# guider-shield.net
KiCad netlist of a schematic drawn in EAGLE
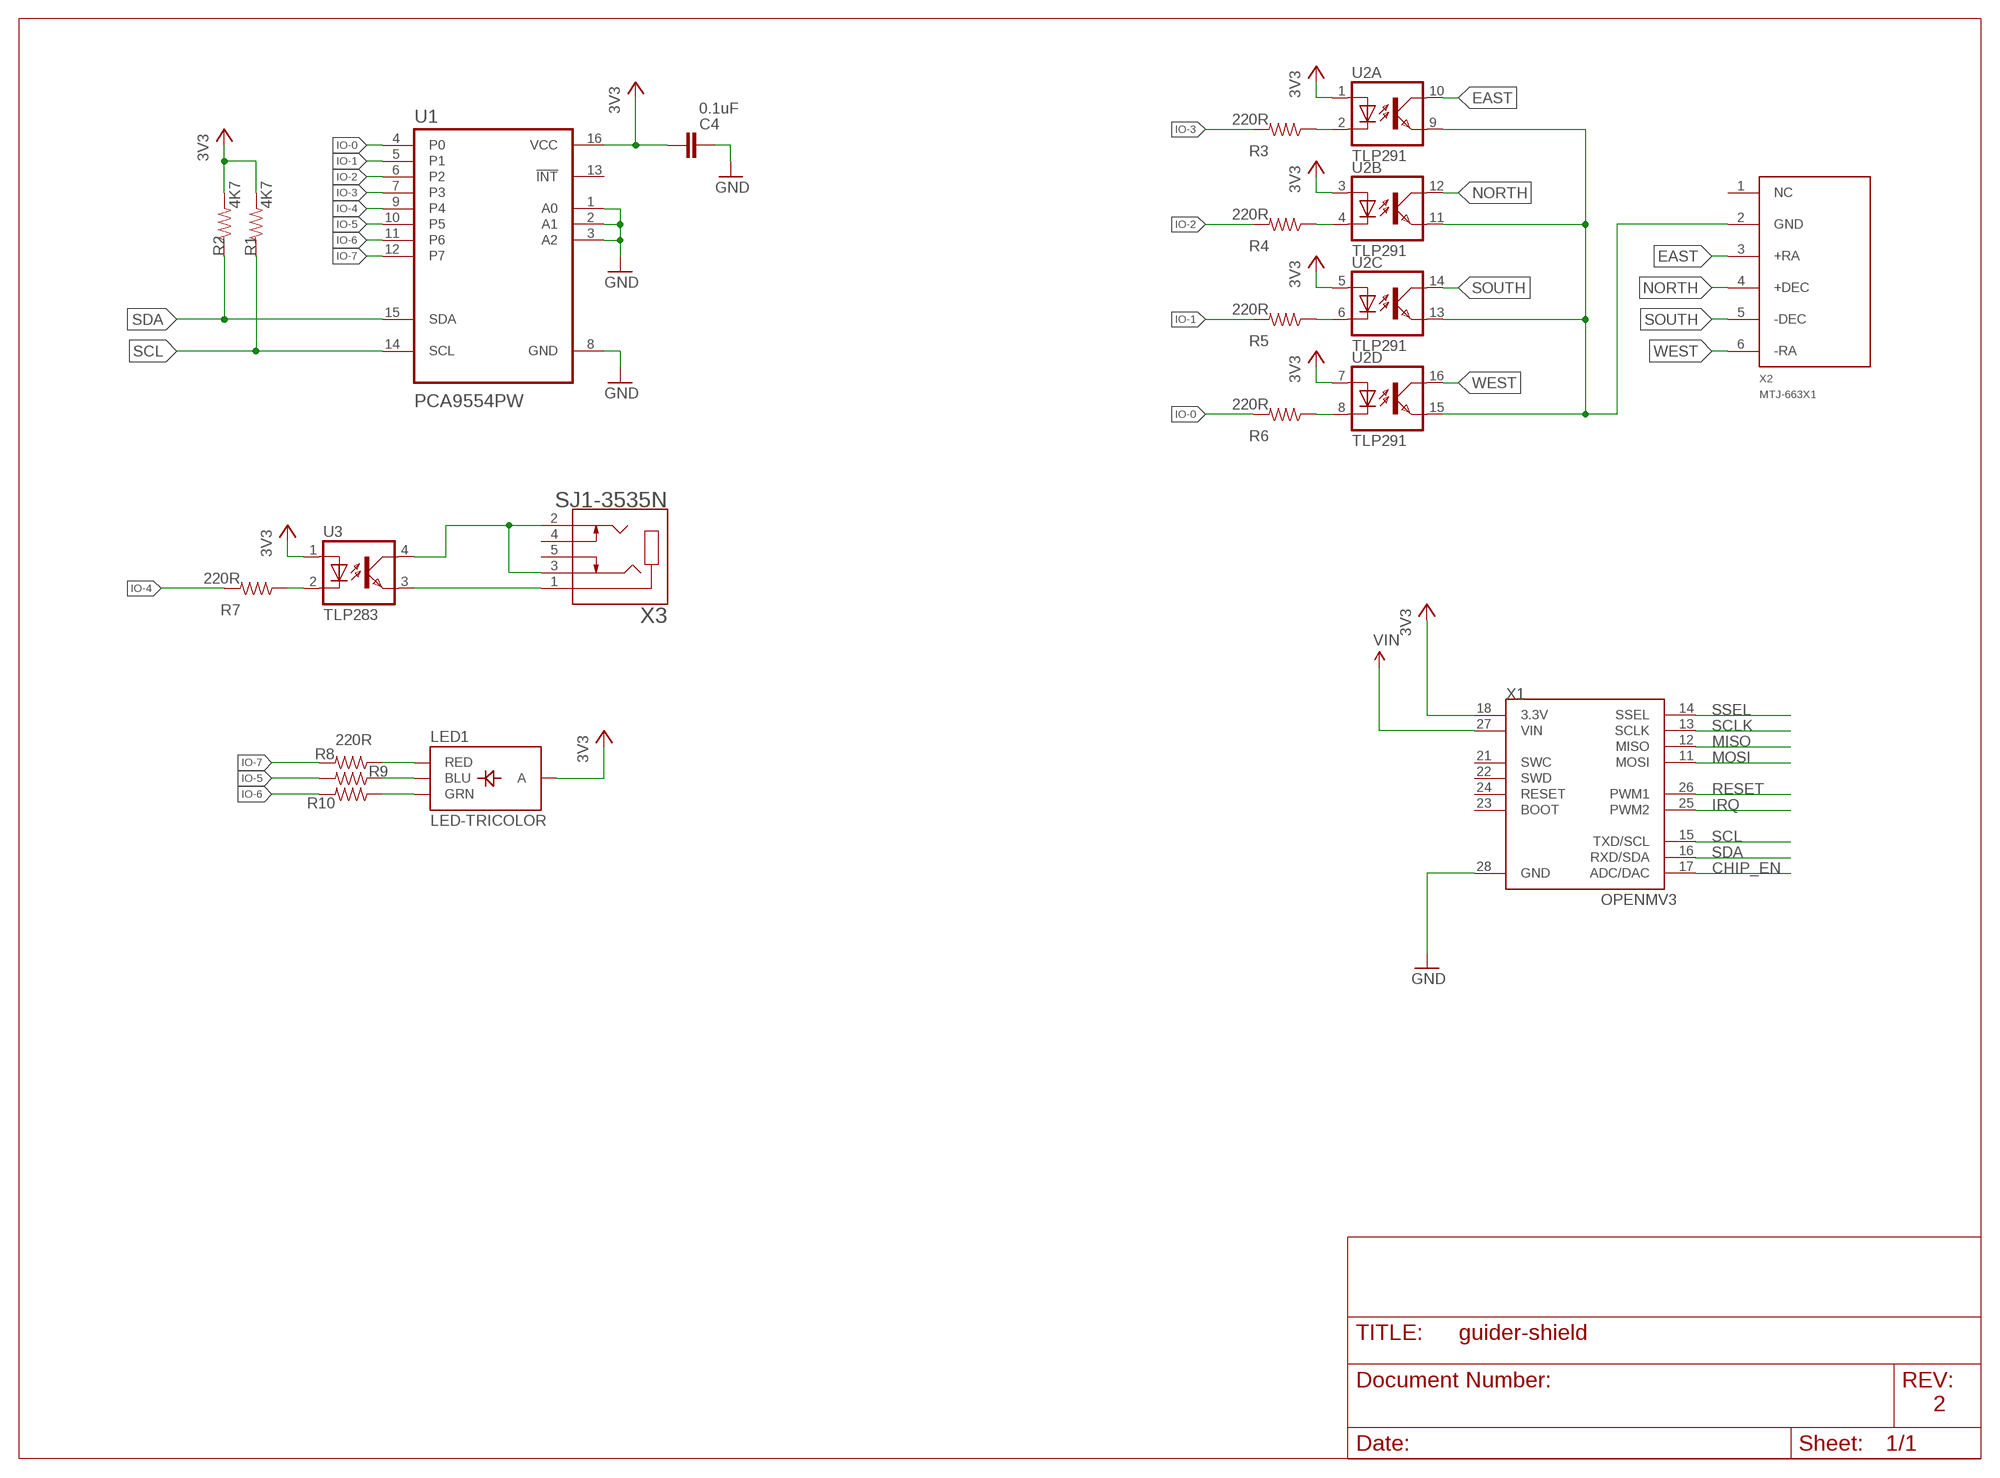
[diagram p0: schematic, sheet 1]

(export (version "E")
  (design (tool "Eeschema 10.0.6"))
  (components
    (comp (ref "C4")
      (value "0.1uF")
      (footprint "eagle-import:0603-CAP")
      (libsource (lib "eagle-import") (part "CAP0603-CAP"))
    )
    (comp (ref "LED1")
      (value "LED-TRICOLOR")
      (footprint "eagle-import:LED-TRICOLOR-SMD")
      (libsource (lib "eagle-import") (part "LED-TRICOLOR"))
    )
    (comp (ref "R1")
      (value "4K7")
      (footprint "eagle-import:0603-RES")
      (libsource (lib "eagle-import") (part "RESISTOR0603-RES"))
    )
    (comp (ref "R2")
      (value "4K7")
      (footprint "eagle-import:0603-RES")
      (libsource (lib "eagle-import") (part "RESISTOR0603-RES"))
    )
    (comp (ref "R3")
      (value "220R")
      (footprint "eagle-import:0603-RES")
      (libsource (lib "eagle-import") (part "RESISTOR0603-RES"))
    )
    (comp (ref "R4")
      (value "220R")
      (footprint "eagle-import:0603-RES")
      (libsource (lib "eagle-import") (part "RESISTOR0603-RES"))
    )
    (comp (ref "R5")
      (value "220R")
      (footprint "eagle-import:0603-RES")
      (libsource (lib "eagle-import") (part "RESISTOR0603-RES"))
    )
    (comp (ref "R6")
      (value "220R")
      (footprint "eagle-import:0603-RES")
      (libsource (lib "eagle-import") (part "RESISTOR0603-RES"))
    )
    (comp (ref "R7")
      (value "220R")
      (footprint "eagle-import:0603-RES")
      (libsource (lib "eagle-import") (part "RESISTOR0603-RES"))
    )
    (comp (ref "R8")
      (value "220R")
      (footprint "eagle-import:0603-RES")
      (libsource (lib "eagle-import") (part "RESISTOR0603-RES"))
    )
    (comp (ref "R9")
      (value "220R")
      (footprint "eagle-import:0603-RES")
      (libsource (lib "eagle-import") (part "RESISTOR0603-RES"))
    )
    (comp (ref "R10")
      (value "220R")
      (footprint "eagle-import:0603-RES")
      (libsource (lib "eagle-import") (part "RESISTOR0603-RES"))
    )
    (comp (ref "U1")
      (value "PCA9554PW")
      (footprint "eagle-import:SOP65P640X120-16N")
      (fields (field (name "MF") "Texas Instruments"))
      (libsource (lib "eagle-import") (part "PCA9554PW"))
    )
    (comp (ref "U2")
      (value "TLP291")
      (footprint "eagle-import:SO016")
      (libsource (lib "eagle-import") (part "TLP283-4-SO016"))
    )
    (comp (ref "U3")
      (value "TLP283")
      (footprint "eagle-import:MINI-FLAT-4")
      (libsource (lib "eagle-import") (part "TLP283"))
    )
    (comp (ref "X1")
      (value "OPENMV3")
      (footprint "eagle-import:OPENMV3")
      (libsource (lib "eagle-import") (part "OPENMV3"))
    )
    (comp (ref "X2")
      (value "MTJ-663X1")
      (footprint "eagle-import:MTJ-663X1")
      (libsource (lib "eagle-import") (part "ST-4-MTJ-663X1"))
    )
    (comp (ref "X3")
      (value "SJ1-3535N")
      (footprint "eagle-import:CUI_SJ1-3535N")
      (fields (field (name "MF") "CUI Devices"))
      (libsource (lib "eagle-import") (part "SJ1-3535N"))
    )
  )
  (nets
    (net (code "1") (name "/CHIP_EN") (class "Default")
      (node (ref "X1") (pin "17") (pinfunction "ADC/DAC_17") (pintype "bidirectional"))
    )
    (net (code "2") (name "/IRQ") (class "Default")
      (node (ref "X1") (pin "25") (pinfunction "PWM2_25") (pintype "bidirectional"))
    )
    (net (code "3") (name "/MISO") (class "Default")
      (node (ref "X1") (pin "12") (pinfunction "MISO_12") (pintype "bidirectional"))
    )
    (net (code "4") (name "/MOSI") (class "Default")
      (node (ref "X1") (pin "11") (pinfunction "MOSI_11") (pintype "bidirectional"))
    )
    (net (code "5") (name "/RESET") (class "Default")
      (node (ref "X1") (pin "26") (pinfunction "PWM1_26") (pintype "bidirectional"))
    )
    (net (code "6") (name "/SCLK") (class "Default")
      (node (ref "X1") (pin "13") (pinfunction "SCLK_13") (pintype "bidirectional"))
    )
    (net (code "7") (name "/SSEL") (class "Default")
      (node (ref "X1") (pin "14") (pinfunction "SSEL_14") (pintype "bidirectional"))
    )
    (net (code "8") (name "3V3") (class "Default")
      (node (ref "C4") (pin "1") (pinfunction "1_1") (pintype "passive"))
      (node (ref "LED1") (pin "A") (pinfunction "A_A") (pintype "bidirectional"))
      (node (ref "R1") (pin "2") (pinfunction "2_2") (pintype "passive"))
      (node (ref "R2") (pin "2") (pinfunction "2_2") (pintype "passive"))
      (node (ref "U1") (pin "16") (pinfunction "VCC_16") (pintype "power_in"))
      (node (ref "U2") (pin "1") (pinfunction "A_1") (pintype "passive"))
      (node (ref "U2") (pin "3") (pinfunction "A_3") (pintype "passive"))
      (node (ref "U2") (pin "5") (pinfunction "A_5") (pintype "passive"))
      (node (ref "U2") (pin "7") (pinfunction "A_7") (pintype "passive"))
      (node (ref "U3") (pin "1") (pinfunction "A_1") (pintype "passive"))
      (node (ref "X1") (pin "18") (pinfunction "3.3V_18") (pintype "power_in"))
    )
    (net (code "9") (name "EAST") (class "Default")
      (node (ref "U2") (pin "10") (pinfunction "COL_10") (pintype "passive"))
      (node (ref "X2") (pin "3") (pinfunction "+RA_3") (pintype "input"))
    )
    (net (code "10") (name "GND") (class "Default")
      (node (ref "C4") (pin "2") (pinfunction "2_2") (pintype "passive"))
      (node (ref "U1") (pin "1") (pinfunction "A0_1") (pintype "input"))
      (node (ref "U1") (pin "2") (pinfunction "A1_2") (pintype "input"))
      (node (ref "U1") (pin "3") (pinfunction "A2_3") (pintype "input"))
      (node (ref "U1") (pin "8") (pinfunction "GND_8") (pintype "power_in"))
      (node (ref "X1") (pin "28") (pinfunction "GND_28") (pintype "power_in"))
    )
    (net (code "11") (name "IO-0") (class "Default")
      (node (ref "R6") (pin "2") (pinfunction "2_2") (pintype "passive"))
      (node (ref "U1") (pin "4") (pinfunction "P0_4") (pintype "bidirectional"))
    )
    (net (code "12") (name "IO-1") (class "Default")
      (node (ref "R5") (pin "2") (pinfunction "2_2") (pintype "passive"))
      (node (ref "U1") (pin "5") (pinfunction "P1_5") (pintype "bidirectional"))
    )
    (net (code "13") (name "IO-2") (class "Default")
      (node (ref "R4") (pin "2") (pinfunction "2_2") (pintype "passive"))
      (node (ref "U1") (pin "6") (pinfunction "P2_6") (pintype "bidirectional"))
    )
    (net (code "14") (name "IO-3") (class "Default")
      (node (ref "R3") (pin "2") (pinfunction "2_2") (pintype "passive"))
      (node (ref "U1") (pin "7") (pinfunction "P3_7") (pintype "bidirectional"))
    )
    (net (code "15") (name "IO-4") (class "Default")
      (node (ref "R7") (pin "2") (pinfunction "2_2") (pintype "passive"))
      (node (ref "U1") (pin "9") (pinfunction "P4_9") (pintype "bidirectional"))
    )
    (net (code "16") (name "IO-5") (class "Default")
      (node (ref "R9") (pin "2") (pinfunction "2_2") (pintype "passive"))
      (node (ref "U1") (pin "10") (pinfunction "P5_10") (pintype "bidirectional"))
    )
    (net (code "17") (name "IO-6") (class "Default")
      (node (ref "R10") (pin "2") (pinfunction "2_2") (pintype "passive"))
      (node (ref "U1") (pin "11") (pinfunction "P6_11") (pintype "bidirectional"))
    )
    (net (code "18") (name "IO-7") (class "Default")
      (node (ref "R8") (pin "2") (pinfunction "2_2") (pintype "passive"))
      (node (ref "U1") (pin "12") (pinfunction "P7_12") (pintype "bidirectional"))
    )
    (net (code "19") (name "NORTH") (class "Default")
      (node (ref "U2") (pin "12") (pinfunction "COL_12") (pintype "passive"))
      (node (ref "X2") (pin "4") (pinfunction "+DEC_4") (pintype "input"))
    )
    (net (code "20") (name "Net-(LED1-BLU)") (class "Default")
      (node (ref "LED1") (pin "B") (pinfunction "BLU_B") (pintype "bidirectional"))
      (node (ref "R9") (pin "1") (pinfunction "1_1") (pintype "passive"))
    )
    (net (code "21") (name "Net-(LED1-GRN)") (class "Default")
      (node (ref "LED1") (pin "G") (pinfunction "GRN_G") (pintype "bidirectional"))
      (node (ref "R10") (pin "1") (pinfunction "1_1") (pintype "passive"))
    )
    (net (code "22") (name "Net-(LED1-RED)") (class "Default")
      (node (ref "LED1") (pin "R") (pinfunction "RED_R") (pintype "bidirectional"))
      (node (ref "R8") (pin "1") (pinfunction "1_1") (pintype "passive"))
    )
    (net (code "23") (name "Net-(U2A-C)") (class "Default")
      (node (ref "R3") (pin "1") (pinfunction "1_1") (pintype "passive"))
      (node (ref "U2") (pin "2") (pinfunction "C_2") (pintype "passive"))
    )
    (net (code "24") (name "Net-(U2A-EMIT)") (class "Default")
      (node (ref "U2") (pin "11") (pinfunction "EMIT_11") (pintype "passive"))
      (node (ref "U2") (pin "13") (pinfunction "EMIT_13") (pintype "passive"))
      (node (ref "U2") (pin "15") (pinfunction "EMIT_15") (pintype "passive"))
      (node (ref "U2") (pin "9") (pinfunction "EMIT_9") (pintype "passive"))
      (node (ref "X2") (pin "2") (pinfunction "GND_2") (pintype "input"))
    )
    (net (code "25") (name "Net-(U2B-C)") (class "Default")
      (node (ref "R4") (pin "1") (pinfunction "1_1") (pintype "passive"))
      (node (ref "U2") (pin "4") (pinfunction "C_4") (pintype "passive"))
    )
    (net (code "26") (name "Net-(U2C-C)") (class "Default")
      (node (ref "R5") (pin "1") (pinfunction "1_1") (pintype "passive"))
      (node (ref "U2") (pin "6") (pinfunction "C_6") (pintype "passive"))
    )
    (net (code "27") (name "Net-(U2D-C)") (class "Default")
      (node (ref "R6") (pin "1") (pinfunction "1_1") (pintype "passive"))
      (node (ref "U2") (pin "8") (pinfunction "C_8") (pintype "passive"))
    )
    (net (code "28") (name "Net-(U3-C)") (class "Default")
      (node (ref "R7") (pin "1") (pinfunction "1_1") (pintype "passive"))
      (node (ref "U3") (pin "2") (pinfunction "C_2") (pintype "passive"))
    )
    (net (code "29") (name "Net-(U3-COL)") (class "Default")
      (node (ref "U3") (pin "4") (pinfunction "COL_4") (pintype "passive"))
      (node (ref "X3") (pin "2") (pinfunction "2_2") (pintype "passive"))
      (node (ref "X3") (pin "3") (pinfunction "3_3") (pintype "passive"))
    )
    (net (code "30") (name "Net-(U3-EMIT)") (class "Default")
      (node (ref "U3") (pin "3") (pinfunction "EMIT_3") (pintype "passive"))
      (node (ref "X3") (pin "1") (pinfunction "1_1") (pintype "passive"))
    )
    (net (code "31") (name "SCL") (class "Default")
      (node (ref "R1") (pin "1") (pinfunction "1_1") (pintype "passive"))
      (node (ref "U1") (pin "14") (pinfunction "SCL_14") (pintype "input"))
      (node (ref "X1") (pin "15") (pinfunction "TXD/SCL_15") (pintype "bidirectional"))
    )
    (net (code "32") (name "SDA") (class "Default")
      (node (ref "R2") (pin "1") (pinfunction "1_1") (pintype "passive"))
      (node (ref "U1") (pin "15") (pinfunction "SDA_15") (pintype "bidirectional"))
      (node (ref "X1") (pin "16") (pinfunction "RXD/SDA_16") (pintype "bidirectional"))
    )
    (net (code "33") (name "SOUTH") (class "Default")
      (node (ref "U2") (pin "14") (pinfunction "COL_14") (pintype "passive"))
      (node (ref "X2") (pin "5") (pinfunction "-DEC_5") (pintype "input"))
    )
    (net (code "34") (name "VIN") (class "Default")
      (node (ref "X1") (pin "27") (pinfunction "VIN_27") (pintype "power_in"))
    )
    (net (code "35") (name "WEST") (class "Default")
      (node (ref "U2") (pin "16") (pinfunction "COL_16") (pintype "passive"))
      (node (ref "X2") (pin "6") (pinfunction "-RA_6") (pintype "input"))
    )
    (net (code "36") (name "unconnected-(U1-~{INT}-Pad13)") (class "Default")
      (node (ref "U1") (pin "13") (pinfunction "~{INT}_13") (pintype "output"))
    )
    (net (code "37") (name "unconnected-(X1-BOOT-Pad23)") (class "Default")
      (node (ref "X1") (pin "23") (pinfunction "BOOT_23") (pintype "bidirectional"))
    )
    (net (code "38") (name "unconnected-(X1-RESET-Pad24)") (class "Default")
      (node (ref "X1") (pin "24") (pinfunction "RESET_24") (pintype "bidirectional"))
    )
    (net (code "39") (name "unconnected-(X1-SWC-Pad21)") (class "Default")
      (node (ref "X1") (pin "21") (pinfunction "SWC_21") (pintype "bidirectional"))
    )
    (net (code "40") (name "unconnected-(X1-SWD-Pad22)") (class "Default")
      (node (ref "X1") (pin "22") (pinfunction "SWD_22") (pintype "bidirectional"))
    )
    (net (code "41") (name "unconnected-(X2-NC-Pad1)") (class "Default")
      (node (ref "X2") (pin "1") (pinfunction "NC_1") (pintype "no_connect"))
    )
    (net (code "42") (name "unconnected-(X3-Pad4)") (class "Default")
      (node (ref "X3") (pin "4") (pinfunction "4_4") (pintype "passive"))
    )
    (net (code "43") (name "unconnected-(X3-Pad5)") (class "Default")
      (node (ref "X3") (pin "5") (pinfunction "5_5") (pintype "passive"))
    )
  )
)
